# oldlight.net
KiCad netlist of a schematic drawn in EAGLE
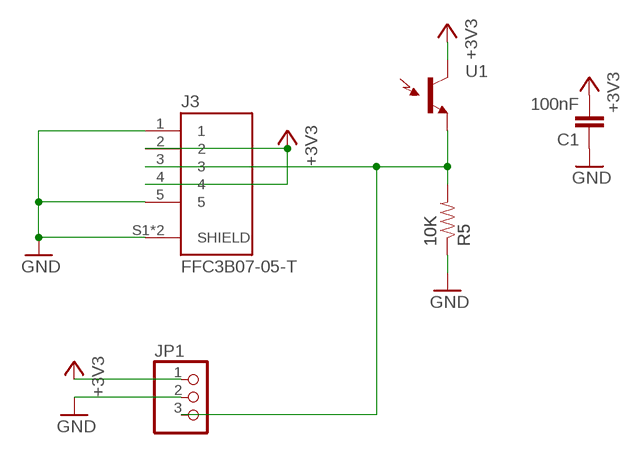
[diagram p0: schematic, sheet 1]

(export (version "E")
  (design (tool "Eeschema 10.0.6"))
  (components
    (comp (ref "C1")
      (value "100nF")
      (footprint "eagle-import:0805")
      (libsource (lib "eagle-import") (part "CAP0805"))
    )
    (comp (ref "J3")
      (value "FFC3B07-05-T")
      (footprint "eagle-import:GCT_FFC3B07-05-T")
      (fields (field (name "MF") "Global Connector Technology"))
      (libsource (lib "eagle-import") (part "FFC3B07-05-T"))
    )
    (comp (ref "JP1")
      (value "PINHD-1X3CB")
      (footprint "eagle-import:1X03-CLEANBIG")
      (libsource (lib "eagle-import") (part "PINHD-1X3CB"))
    )
    (comp (ref "R5")
      (value "10K")
      (footprint "eagle-import:0805")
      (libsource (lib "eagle-import") (part "RESISTOR0805-RES"))
    )
    (comp (ref "U1")
      (value "TEMT6000")
      (footprint "eagle-import:TEMT6000-SEN")
      (libsource (lib "eagle-import") (part "TEMT6000"))
    )
  )
  (nets
    (net (code "1") (name "+3V3") (class "Default")
      (node (ref "C1") (pin "2") (pinfunction "2_2") (pintype "passive"))
      (node (ref "J3") (pin "2") (pinfunction "2_2") (pintype "passive"))
      (node (ref "J3") (pin "4") (pinfunction "4_4") (pintype "passive"))
      (node (ref "JP1") (pin "1") (pinfunction "1_1") (pintype "passive"))
      (node (ref "U1") (pin "COLLECTOR") (pinfunction "C1_COLLECTOR") (pintype "passive"))
    )
    (net (code "2") (name "GND") (class "Default")
      (node (ref "C1") (pin "1") (pinfunction "1_1") (pintype "passive"))
      (node (ref "J3") (pin "1") (pinfunction "1_1") (pintype "passive"))
      (node (ref "J3") (pin "5") (pinfunction "5_5") (pintype "passive"))
      (node (ref "J3") (pin "S1") (pinfunction "SHIELD_S1") (pintype "passive"))
      (node (ref "J3") (pin "S2") (pinfunction "SHIELD_S2") (pintype "passive"))
      (node (ref "JP1") (pin "2") (pinfunction "2_2") (pintype "passive"))
      (node (ref "R5") (pin "1") (pinfunction "1_1") (pintype "passive"))
    )
    (net (code "3") (name "Net-(U1-E1)") (class "Default")
      (node (ref "J3") (pin "3") (pinfunction "3_3") (pintype "passive"))
      (node (ref "JP1") (pin "3") (pinfunction "3_3") (pintype "passive"))
      (node (ref "R5") (pin "2") (pinfunction "2_2") (pintype "passive"))
      (node (ref "U1") (pin "EMITTER") (pinfunction "E1_EMITTER") (pintype "passive"))
    )
  )
)
